# Conn_pcb2.net
KiCad netlist of a schematic drawn in EAGLE
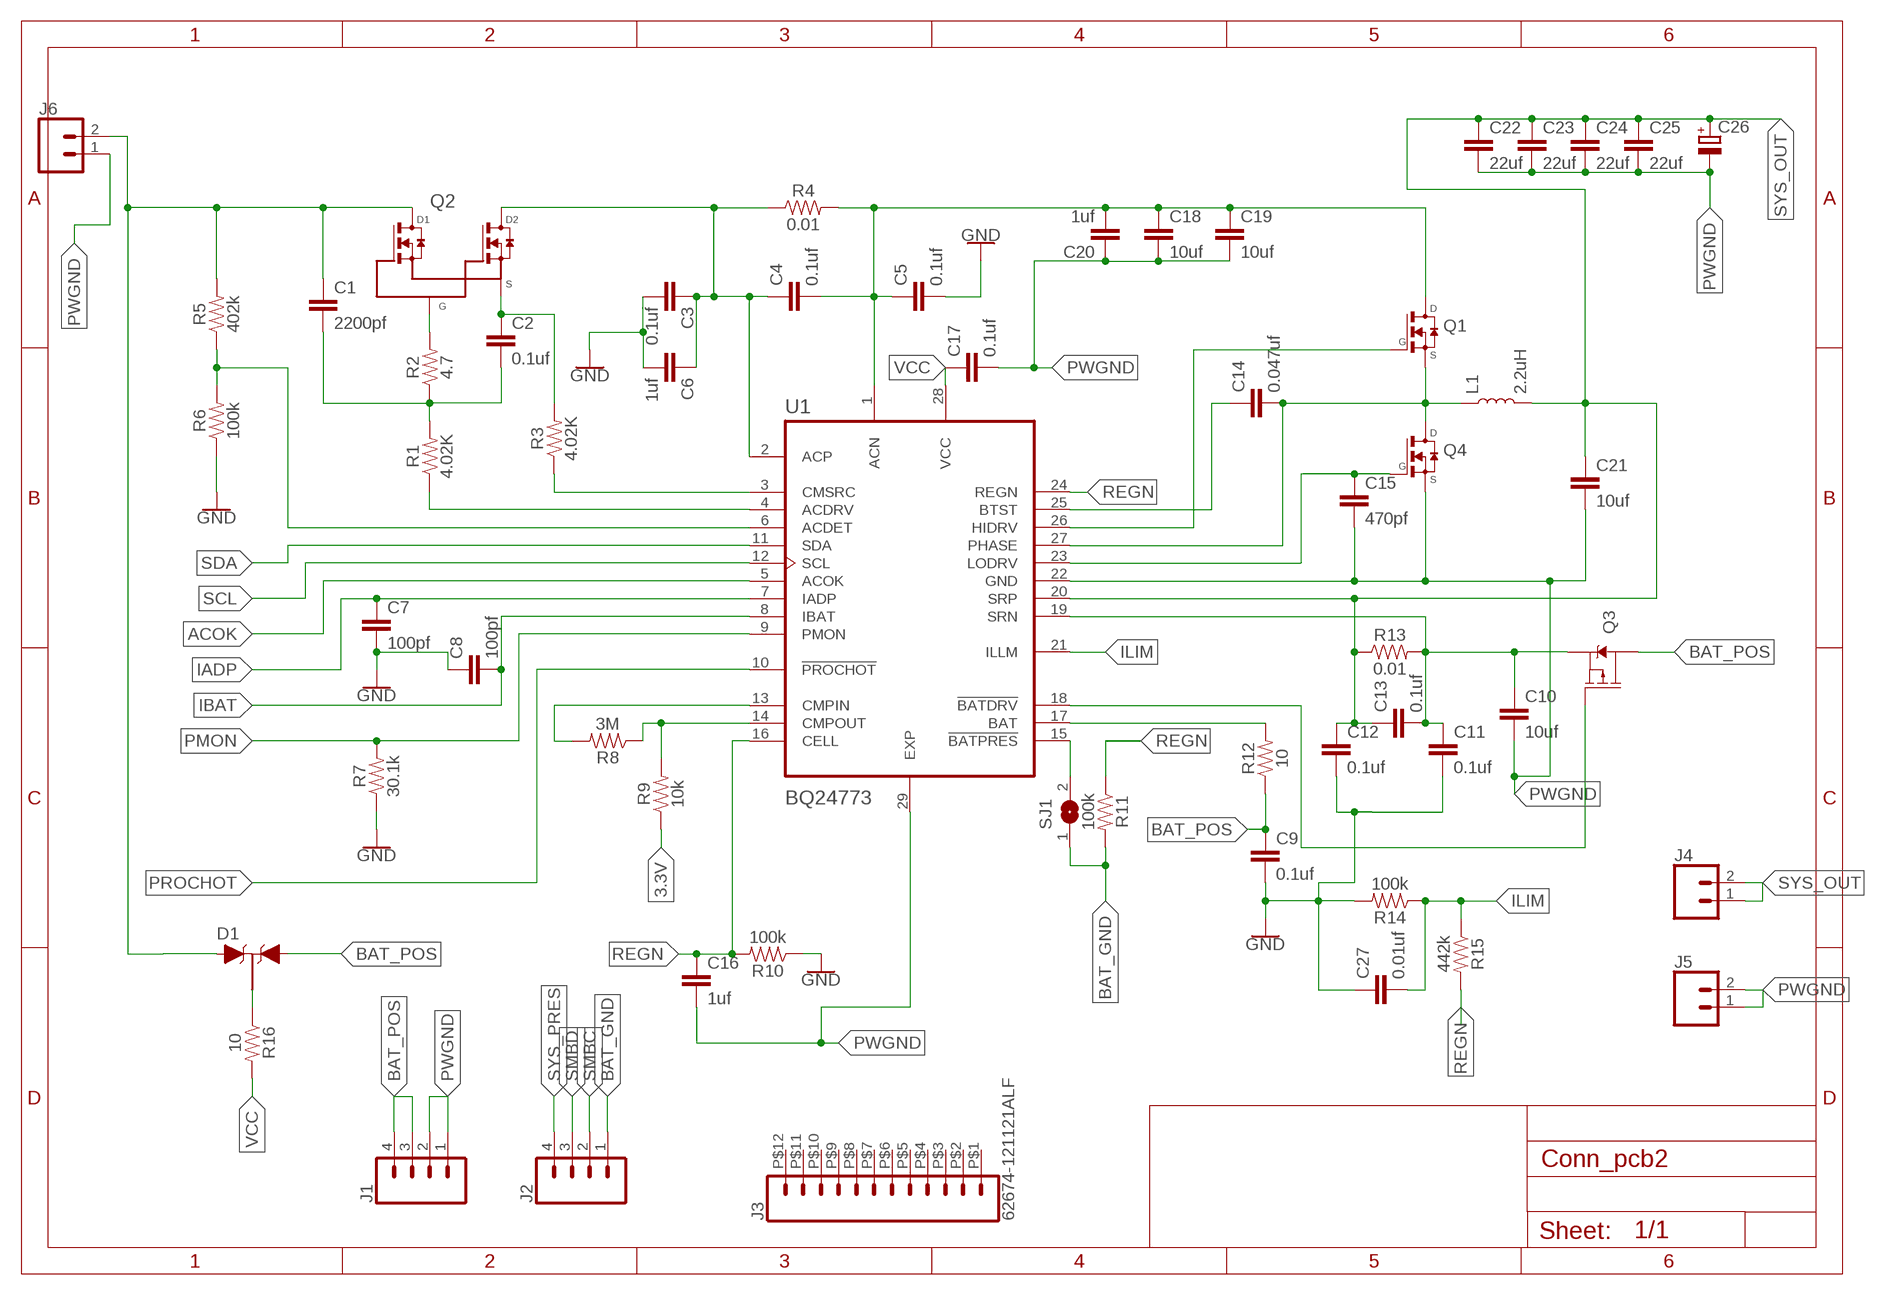
[diagram p0: schematic, sheet 1]

(export (version "E")
  (design (tool "Eeschema 10.0.6"))
  (components
    (comp (ref "C1")
      (value "2200pf")
      (footprint "eagle-import:CAPC1005X50")
      (libsource (lib "eagle-import") (part "CAP0402"))
    )
    (comp (ref "C2")
      (value "0.1uf")
      (footprint "eagle-import:CAPC1005X50")
      (libsource (lib "eagle-import") (part "CAP0402"))
    )
    (comp (ref "C3")
      (value "0.1uf")
      (footprint "eagle-import:CAPC1005X50")
      (libsource (lib "eagle-import") (part "CAP0402"))
    )
    (comp (ref "C4")
      (value "0.1uf")
      (footprint "eagle-import:CAPC1005X50")
      (libsource (lib "eagle-import") (part "CAP0402"))
    )
    (comp (ref "C5")
      (value "0.1uf")
      (footprint "eagle-import:CAPC1005X50")
      (libsource (lib "eagle-import") (part "CAP0402"))
    )
    (comp (ref "C6")
      (value "1uf")
      (footprint "eagle-import:CAPC1005X50")
      (libsource (lib "eagle-import") (part "CAP0402"))
    )
    (comp (ref "C7")
      (value "100pf")
      (footprint "eagle-import:CAPC1005X50")
      (libsource (lib "eagle-import") (part "CAP0402"))
    )
    (comp (ref "C8")
      (value "100pf")
      (footprint "eagle-import:CAPC1005X50")
      (libsource (lib "eagle-import") (part "CAP0402"))
    )
    (comp (ref "C9")
      (value "0.1uf")
      (footprint "eagle-import:CAPC1005X50")
      (libsource (lib "eagle-import") (part "CAP0402"))
    )
    (comp (ref "C10")
      (value "10uf")
      (footprint "eagle-import:C0805K")
      (libsource (lib "eagle-import") (part "C-EUC0805K"))
    )
    (comp (ref "C11")
      (value "0.1uf")
      (footprint "eagle-import:CAPC1005X50")
      (libsource (lib "eagle-import") (part "CAP0402"))
    )
    (comp (ref "C12")
      (value "0.1uf")
      (footprint "eagle-import:CAPC1005X50")
      (libsource (lib "eagle-import") (part "CAP0402"))
    )
    (comp (ref "C13")
      (value "0.1uf")
      (footprint "eagle-import:CAPC1005X50")
      (libsource (lib "eagle-import") (part "CAP0402"))
    )
    (comp (ref "C14")
      (value "0.047uf")
      (footprint "eagle-import:CAPC1005X50")
      (libsource (lib "eagle-import") (part "CAP0402"))
    )
    (comp (ref "C15")
      (value "470pf")
      (footprint "eagle-import:CAPC1005X50")
      (libsource (lib "eagle-import") (part "CAP0402"))
    )
    (comp (ref "C16")
      (value "1uf")
      (footprint "eagle-import:CAPC1005X50")
      (libsource (lib "eagle-import") (part "CAP0402"))
    )
    (comp (ref "C17")
      (value "0.1uf")
      (footprint "eagle-import:CAPC1005X50")
      (libsource (lib "eagle-import") (part "CAP0402"))
    )
    (comp (ref "C18")
      (value "10uf")
      (footprint "eagle-import:C0805K")
      (libsource (lib "eagle-import") (part "C-EUC0805K"))
    )
    (comp (ref "C19")
      (value "10uf")
      (footprint "eagle-import:C0805K")
      (libsource (lib "eagle-import") (part "C-EUC0805K"))
    )
    (comp (ref "C20")
      (value "1uf")
      (footprint "eagle-import:CAPC1005X50")
      (libsource (lib "eagle-import") (part "CAP0402"))
    )
    (comp (ref "C21")
      (value "10uf")
      (footprint "eagle-import:C0805K")
      (libsource (lib "eagle-import") (part "C-EUC0805K"))
    )
    (comp (ref "C22")
      (value "22uf")
      (footprint "eagle-import:C1206")
      (libsource (lib "eagle-import") (part "C-EUC1206"))
    )
    (comp (ref "C23")
      (value "22uf")
      (footprint "eagle-import:C1206")
      (libsource (lib "eagle-import") (part "C-EUC1206"))
    )
    (comp (ref "C24")
      (value "22uf")
      (footprint "eagle-import:C1206")
      (libsource (lib "eagle-import") (part "C-EUC1206"))
    )
    (comp (ref "C25")
      (value "22uf")
      (footprint "eagle-import:C1206")
      (libsource (lib "eagle-import") (part "C-EUC1206"))
    )
    (comp (ref "C26")
      (value "CPOL-EUF")
      (footprint "eagle-import:PANASONIC_F")
      (libsource (lib "eagle-import") (part "CPOL-EUF"))
    )
    (comp (ref "C27")
      (value "0.01uf")
      (footprint "eagle-import:CAPC1005X50")
      (libsource (lib "eagle-import") (part "CAP0402"))
    )
    (comp (ref "D1")
      (value "BAT54C-7-F")
      (footprint "eagle-import:SOT95P235X110-3")
      (libsource (lib "eagle-import") (part "BAT54C-7-F"))
    )
    (comp (ref "J1")
      (value "CONN_041.3")
      (footprint "eagle-import:1X04_NO_SILK_1.3")
      (libsource (lib "eagle-import") (part "CONN_041.3"))
    )
    (comp (ref "J2")
      (value "CONN_041.3")
      (footprint "eagle-import:1X04_NO_SILK_1.3")
      (libsource (lib "eagle-import") (part "CONN_041.3"))
    )
    (comp (ref "J3")
      (value "62674-121121ALF")
      (footprint "eagle-import:62674-121121ALF")
      (libsource (lib "eagle-import") (part "62674-121121ALF"))
    )
    (comp (ref "J4")
      (value "CONN_021.4HOLE")
      (footprint "eagle-import:1X02_1.4HOLE")
      (libsource (lib "eagle-import") (part "CONN_021.4HOLE"))
    )
    (comp (ref "J5")
      (value "CONN_021.4HOLE")
      (footprint "eagle-import:1X02_1.4HOLE")
      (libsource (lib "eagle-import") (part "CONN_021.4HOLE"))
    )
    (comp (ref "J6")
      (value "CONN_021.4HOLE")
      (footprint "eagle-import:1X02_1.4HOLE")
      (libsource (lib "eagle-import") (part "CONN_021.4HOLE"))
    )
    (comp (ref "L1")
      (value "2.2uH")
      (footprint "eagle-import:RESM6365X610")
      (libsource (lib "eagle-import") (part "XEL6060-222MEB"))
    )
    (comp (ref "Q1")
      (value "CSD17308Q3")
      (footprint "eagle-import:SON65P330X330X110-8")
      (fields (field (name "SPICEPREFIX") "Q"))
      (libsource (lib "eagle-import") (part "CSD17308Q3"))
    )
    (comp (ref "Q2")
      (value "CSD87312Q3EVSON")
      (footprint "eagle-import:QFN65P330X330X100-12")
      (libsource (lib "eagle-import") (part "CSD87312Q3EVSON"))
    )
    (comp (ref "Q3")
      (value "CSD25402Q3A")
      (footprint "eagle-import:CSD25402Q3A")
      (libsource (lib "eagle-import") (part "CSD25402Q3A"))
    )
    (comp (ref "Q4")
      (value "CSD17308Q3")
      (footprint "eagle-import:SON65P330X330X110-8")
      (fields (field (name "SPICEPREFIX") "Q"))
      (libsource (lib "eagle-import") (part "CSD17308Q3"))
    )
    (comp (ref "R1")
      (value "4.02K")
      (footprint "eagle-import:0402")
      (libsource (lib "eagle-import") (part "RES4K04020402"))
    )
    (comp (ref "R2")
      (value "4.7")
      (footprint "eagle-import:0402")
      (libsource (lib "eagle-import") (part "RES4K04020402"))
    )
    (comp (ref "R3")
      (value "4.02K")
      (footprint "eagle-import:0402")
      (libsource (lib "eagle-import") (part "RES4K04020402"))
    )
    (comp (ref "R4")
      (value "0.01")
      (footprint "eagle-import:1206")
      (libsource (lib "eagle-import") (part "SENSE-RES"))
    )
    (comp (ref "R5")
      (value "402k")
      (footprint "eagle-import:0402")
      (libsource (lib "eagle-import") (part "RES4K04020402"))
    )
    (comp (ref "R6")
      (value "100k")
      (footprint "eagle-import:0402")
      (libsource (lib "eagle-import") (part "RES4K04020402"))
    )
    (comp (ref "R7")
      (value "30.1k")
      (footprint "eagle-import:0402")
      (libsource (lib "eagle-import") (part "RES4K04020402"))
    )
    (comp (ref "R8")
      (value "3M")
      (footprint "eagle-import:0402")
      (libsource (lib "eagle-import") (part "RES4K04020402"))
    )
    (comp (ref "R9")
      (value "10k")
      (footprint "eagle-import:0402")
      (libsource (lib "eagle-import") (part "RES4K04020402"))
    )
    (comp (ref "R10")
      (value "100k")
      (footprint "eagle-import:0402")
      (libsource (lib "eagle-import") (part "RES4K04020402"))
    )
    (comp (ref "R11")
      (value "100k")
      (footprint "eagle-import:0402")
      (libsource (lib "eagle-import") (part "RES4K04020402"))
    )
    (comp (ref "R12")
      (value "10")
      (footprint "eagle-import:0402")
      (libsource (lib "eagle-import") (part "RES4K04020402"))
    )
    (comp (ref "R13")
      (value "0.01")
      (footprint "eagle-import:1206")
      (libsource (lib "eagle-import") (part "SENSE-RES"))
    )
    (comp (ref "R14")
      (value "100k")
      (footprint "eagle-import:0402")
      (libsource (lib "eagle-import") (part "RES4K04020402"))
    )
    (comp (ref "R15")
      (value "442k")
      (footprint "eagle-import:0402")
      (libsource (lib "eagle-import") (part "RES4K04020402"))
    )
    (comp (ref "R16")
      (value "10")
      (footprint "eagle-import:0402")
      (libsource (lib "eagle-import") (part "RES4K04020402"))
    )
    (comp (ref "SJ1") (value "SJ") (footprint "eagle-import:SJ") (libsource (lib "eagle-import") (part "SJ")))
    (comp (ref "U1")
      (value "BQ24773")
      (footprint "eagle-import:QFN40P400X400X80-29T240")
      (libsource (lib "eagle-import") (part "BQ24773"))
    )
  )
  (nets
    (net (code "1") (name "3.3V") (class "Default")
      (node (ref "R9") (pin "1") (pinfunction "1_1") (pintype "passive"))
    )
    (net (code "2") (name "ACOK") (class "Default")
      (node (ref "U1") (pin "5") (pinfunction "ACOK_5") (pintype "output"))
    )
    (net (code "3") (name "BAT_GND") (class "Default")
      (node (ref "J2") (pin "1") (pinfunction "1_1") (pintype "passive"))
      (node (ref "R11") (pin "2") (pinfunction "2_2") (pintype "passive"))
      (node (ref "SJ1") (pin "1") (pinfunction "1_1") (pintype "passive"))
    )
    (net (code "4") (name "BAT_POS") (class "Default")
      (node (ref "C9") (pin "1") (pinfunction "1_1") (pintype "passive"))
      (node (ref "D1") (pin "2") (pinfunction "A2_2") (pintype "passive"))
      (node (ref "J1") (pin "3") (pinfunction "3_3") (pintype "passive"))
      (node (ref "J1") (pin "4") (pinfunction "4_4") (pintype "passive"))
      (node (ref "Q3") (pin "1") (pinfunction "D_1") (pintype "bidirectional"))
      (node (ref "Q3") (pin "2") (pinfunction "D_2") (pintype "bidirectional"))
      (node (ref "Q3") (pin "3") (pinfunction "D_3") (pintype "bidirectional"))
      (node (ref "R12") (pin "1") (pinfunction "1_1") (pintype "passive"))
    )
    (net (code "5") (name "GND") (class "Default")
      (node (ref "C11") (pin "2") (pinfunction "2_2") (pintype "passive"))
      (node (ref "C12") (pin "2") (pinfunction "2_2") (pintype "passive"))
      (node (ref "C27") (pin "1") (pinfunction "1_1") (pintype "passive"))
      (node (ref "C3") (pin "2") (pinfunction "2_2") (pintype "passive"))
      (node (ref "C5") (pin "2") (pinfunction "2_2") (pintype "passive"))
      (node (ref "C6") (pin "2") (pinfunction "2_2") (pintype "passive"))
      (node (ref "C7") (pin "2") (pinfunction "2_2") (pintype "passive"))
      (node (ref "C8") (pin "1") (pinfunction "1_1") (pintype "passive"))
      (node (ref "C9") (pin "2") (pinfunction "2_2") (pintype "passive"))
      (node (ref "R10") (pin "1") (pinfunction "1_1") (pintype "passive"))
      (node (ref "R14") (pin "2") (pinfunction "2_2") (pintype "passive"))
      (node (ref "R6") (pin "1") (pinfunction "1_1") (pintype "passive"))
      (node (ref "R7") (pin "1") (pinfunction "1_1") (pintype "passive"))
    )
    (net (code "6") (name "IADP") (class "Default")
      (node (ref "C7") (pin "1") (pinfunction "1_1") (pintype "passive"))
      (node (ref "U1") (pin "7") (pinfunction "IADP_7") (pintype "output"))
    )
    (net (code "7") (name "IBAT") (class "Default")
      (node (ref "C8") (pin "2") (pinfunction "2_2") (pintype "passive"))
      (node (ref "U1") (pin "8") (pinfunction "IBAT_8") (pintype "output"))
    )
    (net (code "8") (name "ILIM") (class "Default")
      (node (ref "C27") (pin "2") (pinfunction "2_2") (pintype "passive"))
      (node (ref "R14") (pin "1") (pinfunction "1_1") (pintype "passive"))
      (node (ref "R15") (pin "1") (pinfunction "1_1") (pintype "passive"))
      (node (ref "U1") (pin "21") (pinfunction "ILLM_21") (pintype "input"))
    )
    (net (code "9") (name "Net-(C1-Pad2)") (class "Default")
      (node (ref "C1") (pin "2") (pinfunction "2_2") (pintype "passive"))
      (node (ref "C2") (pin "2") (pinfunction "2_2") (pintype "passive"))
      (node (ref "R1") (pin "2") (pinfunction "2_2") (pintype "passive"))
      (node (ref "R2") (pin "1") (pinfunction "1_1") (pintype "passive"))
    )
    (net (code "10") (name "Net-(C2-Pad1)") (class "Default")
      (node (ref "C2") (pin "1") (pinfunction "1_1") (pintype "passive"))
      (node (ref "Q2") (pin "9") (pinfunction "S_9") (pintype "passive"))
      (node (ref "Q2") (pin "9.1") (pinfunction "S_9.1") (pintype "passive"))
      (node (ref "Q2") (pin "9.2") (pinfunction "S_9.2") (pintype "passive"))
      (node (ref "Q2") (pin "9.3") (pinfunction "S_9.3") (pintype "passive"))
      (node (ref "Q2") (pin "9.4") (pinfunction "S_9.4") (pintype "passive"))
      (node (ref "R3") (pin "2") (pinfunction "2_2") (pintype "passive"))
    )
    (net (code "11") (name "Net-(D1-A1)") (class "Default")
      (node (ref "C1") (pin "1") (pinfunction "1_1") (pintype "passive"))
      (node (ref "D1") (pin "1") (pinfunction "A1_1") (pintype "passive"))
      (node (ref "J6") (pin "2") (pinfunction "2_2") (pintype "passive"))
      (node (ref "Q2") (pin "1") (pinfunction "D1_1") (pintype "passive"))
      (node (ref "Q2") (pin "3") (pinfunction "D1_3") (pintype "passive"))
      (node (ref "Q2") (pin "4") (pinfunction "D1_4") (pintype "passive"))
      (node (ref "R5") (pin "2") (pinfunction "2_2") (pintype "passive"))
    )
    (net (code "12") (name "Net-(D1-K)") (class "Default")
      (node (ref "D1") (pin "3") (pinfunction "K_3") (pintype "passive"))
      (node (ref "R16") (pin "1") (pinfunction "1_1") (pintype "passive"))
    )
    (net (code "13") (name "Net-(Q1-G)") (class "Default")
      (node (ref "Q1") (pin "4") (pinfunction "G_4") (pintype "passive"))
      (node (ref "U1") (pin "26") (pinfunction "HIDRV_26") (pintype "output"))
    )
    (net (code "14") (name "Net-(Q2-G)") (class "Default")
      (node (ref "Q2") (pin "5") (pinfunction "G_5") (pintype "passive"))
      (node (ref "R2") (pin "2") (pinfunction "2_2") (pintype "passive"))
    )
    (net (code "15") (name "Net-(Q3-G)") (class "Default")
      (node (ref "Q3") (pin "4") (pinfunction "G_4") (pintype "bidirectional"))
      (node (ref "U1") (pin "18") (pinfunction "~{BATDRV}_18") (pintype "output"))
    )
    (net (code "16") (name "Net-(Q4-G)") (class "Default")
      (node (ref "C15") (pin "1") (pinfunction "1_1") (pintype "passive"))
      (node (ref "Q4") (pin "4") (pinfunction "G_4") (pintype "passive"))
      (node (ref "U1") (pin "23") (pinfunction "LODRV_23") (pintype "output"))
    )
    (net (code "17") (name "Net-(U1-ACDET)") (class "Default")
      (node (ref "R5") (pin "1") (pinfunction "1_1") (pintype "passive"))
      (node (ref "R6") (pin "2") (pinfunction "2_2") (pintype "passive"))
      (node (ref "U1") (pin "6") (pinfunction "ACDET_6") (pintype "input"))
    )
    (net (code "18") (name "Net-(U1-ACDRV)") (class "Default")
      (node (ref "R1") (pin "1") (pinfunction "1_1") (pintype "passive"))
      (node (ref "U1") (pin "4") (pinfunction "ACDRV_4") (pintype "output"))
    )
    (net (code "19") (name "Net-(U1-ACN)") (class "Default")
      (node (ref "C18") (pin "1") (pinfunction "1_1") (pintype "passive"))
      (node (ref "C19") (pin "1") (pinfunction "1_1") (pintype "passive"))
      (node (ref "C20") (pin "2") (pinfunction "2_2") (pintype "passive"))
      (node (ref "C4") (pin "2") (pinfunction "2_2") (pintype "passive"))
      (node (ref "C5") (pin "1") (pinfunction "1_1") (pintype "passive"))
      (node (ref "Q1") (pin "5") (pinfunction "D_5") (pintype "passive"))
      (node (ref "Q1") (pin "6") (pinfunction "D_6") (pintype "passive"))
      (node (ref "Q1") (pin "7") (pinfunction "D_7") (pintype "passive"))
      (node (ref "Q1") (pin "8") (pinfunction "D_8") (pintype "passive"))
      (node (ref "R4") (pin "2") (pinfunction "2_2") (pintype "passive"))
      (node (ref "U1") (pin "1") (pinfunction "ACN_1") (pintype "input"))
    )
    (net (code "20") (name "Net-(U1-ACP)") (class "Default")
      (node (ref "C3") (pin "1") (pinfunction "1_1") (pintype "passive"))
      (node (ref "C4") (pin "1") (pinfunction "1_1") (pintype "passive"))
      (node (ref "C6") (pin "1") (pinfunction "1_1") (pintype "passive"))
      (node (ref "Q2") (pin "6") (pinfunction "D2_6") (pintype "passive"))
      (node (ref "Q2") (pin "7") (pinfunction "D2_7") (pintype "passive"))
      (node (ref "Q2") (pin "8") (pinfunction "D2_8") (pintype "passive"))
      (node (ref "R4") (pin "1") (pinfunction "1_1") (pintype "passive"))
      (node (ref "U1") (pin "2") (pinfunction "ACP_2") (pintype "input"))
    )
    (net (code "21") (name "Net-(U1-BAT)") (class "Default")
      (node (ref "R12") (pin "2") (pinfunction "2_2") (pintype "passive"))
      (node (ref "U1") (pin "17") (pinfunction "BAT_17") (pintype "input"))
    )
    (net (code "22") (name "Net-(U1-BTST)") (class "Default")
      (node (ref "C14") (pin "1") (pinfunction "1_1") (pintype "passive"))
      (node (ref "U1") (pin "25") (pinfunction "BTST_25") (pintype "passive"))
    )
    (net (code "23") (name "Net-(U1-CMPIN)") (class "Default")
      (node (ref "R8") (pin "2") (pinfunction "2_2") (pintype "passive"))
      (node (ref "U1") (pin "13") (pinfunction "CMPIN_13") (pintype "input"))
    )
    (net (code "24") (name "Net-(U1-CMPOUT)") (class "Default")
      (node (ref "R8") (pin "1") (pinfunction "1_1") (pintype "passive"))
      (node (ref "R9") (pin "2") (pinfunction "2_2") (pintype "passive"))
      (node (ref "U1") (pin "14") (pinfunction "CMPOUT_14") (pintype "output"))
    )
    (net (code "25") (name "Net-(U1-CMSRC)") (class "Default")
      (node (ref "R3") (pin "1") (pinfunction "1_1") (pintype "passive"))
      (node (ref "U1") (pin "3") (pinfunction "CMSRC_3") (pintype "input"))
    )
    (net (code "26") (name "Net-(U1-PHASE)") (class "Default")
      (node (ref "C14") (pin "2") (pinfunction "2_2") (pintype "passive"))
      (node (ref "L1") (pin "1") (pinfunction "1_1") (pintype "passive"))
      (node (ref "Q1") (pin "1") (pinfunction "S_1") (pintype "passive"))
      (node (ref "Q1") (pin "2") (pinfunction "S_2") (pintype "passive"))
      (node (ref "Q1") (pin "3") (pinfunction "S_3") (pintype "passive"))
      (node (ref "Q4") (pin "5") (pinfunction "D_5") (pintype "passive"))
      (node (ref "Q4") (pin "6") (pinfunction "D_6") (pintype "passive"))
      (node (ref "Q4") (pin "7") (pinfunction "D_7") (pintype "passive"))
      (node (ref "Q4") (pin "8") (pinfunction "D_8") (pintype "passive"))
      (node (ref "U1") (pin "27") (pinfunction "PHASE_27") (pintype "output"))
    )
    (net (code "27") (name "Net-(U1-SRN)") (class "Default")
      (node (ref "C10") (pin "1") (pinfunction "1_1") (pintype "passive"))
      (node (ref "C11") (pin "1") (pinfunction "1_1") (pintype "passive"))
      (node (ref "C13") (pin "2") (pinfunction "2_2") (pintype "passive"))
      (node (ref "Q3") (pin "5") (pinfunction "S_5") (pintype "bidirectional"))
      (node (ref "Q3") (pin "6") (pinfunction "S_6") (pintype "bidirectional"))
      (node (ref "Q3") (pin "7") (pinfunction "S_7") (pintype "bidirectional"))
      (node (ref "Q3") (pin "8") (pinfunction "S_8") (pintype "bidirectional"))
      (node (ref "Q3") (pin "9") (pinfunction "S_9") (pintype "bidirectional"))
      (node (ref "R13") (pin "2") (pinfunction "2_2") (pintype "passive"))
      (node (ref "U1") (pin "19") (pinfunction "SRN_19") (pintype "input"))
    )
    (net (code "28") (name "Net-(U1-~{BATPRES})") (class "Default")
      (node (ref "SJ1") (pin "2") (pinfunction "2_2") (pintype "passive"))
      (node (ref "U1") (pin "15") (pinfunction "~{BATPRES}_15") (pintype "input"))
    )
    (net (code "29") (name "PMON") (class "Default")
      (node (ref "R7") (pin "2") (pinfunction "2_2") (pintype "passive"))
      (node (ref "U1") (pin "9") (pinfunction "PMON_9") (pintype "output"))
    )
    (net (code "30") (name "PROCHOT") (class "Default")
      (node (ref "U1") (pin "10") (pinfunction "~{PROCHOT}_10") (pintype "output"))
    )
    (net (code "31") (name "PWGND") (class "Default")
      (node (ref "C10") (pin "2") (pinfunction "2_2") (pintype "passive"))
      (node (ref "C15") (pin "2") (pinfunction "2_2") (pintype "passive"))
      (node (ref "C16") (pin "2") (pinfunction "2_2") (pintype "passive"))
      (node (ref "C17") (pin "2") (pinfunction "2_2") (pintype "passive"))
      (node (ref "C18") (pin "2") (pinfunction "2_2") (pintype "passive"))
      (node (ref "C19") (pin "2") (pinfunction "2_2") (pintype "passive"))
      (node (ref "C20") (pin "1") (pinfunction "1_1") (pintype "passive"))
      (node (ref "C21") (pin "2") (pinfunction "2_2") (pintype "passive"))
      (node (ref "C22") (pin "2") (pinfunction "2_2") (pintype "passive"))
      (node (ref "C23") (pin "2") (pinfunction "2_2") (pintype "passive"))
      (node (ref "C24") (pin "2") (pinfunction "2_2") (pintype "passive"))
      (node (ref "C25") (pin "2") (pinfunction "2_2") (pintype "passive"))
      (node (ref "C26") (pin "-") (pinfunction "-_-") (pintype "passive"))
      (node (ref "J1") (pin "1") (pinfunction "1_1") (pintype "passive"))
      (node (ref "J1") (pin "2") (pinfunction "2_2") (pintype "passive"))
      (node (ref "J5") (pin "1") (pinfunction "1_1") (pintype "passive"))
      (node (ref "J5") (pin "2") (pinfunction "2_2") (pintype "passive"))
      (node (ref "J6") (pin "1") (pinfunction "1_1") (pintype "passive"))
      (node (ref "Q4") (pin "1") (pinfunction "S_1") (pintype "passive"))
      (node (ref "Q4") (pin "2") (pinfunction "S_2") (pintype "passive"))
      (node (ref "Q4") (pin "3") (pinfunction "S_3") (pintype "passive"))
      (node (ref "U1") (pin "22") (pinfunction "GND_22") (pintype "power_in"))
      (node (ref "U1") (pin "29") (pinfunction "EXP_29") (pintype "power_in"))
    )
    (net (code "32") (name "REGN") (class "Default")
      (node (ref "C16") (pin "1") (pinfunction "1_1") (pintype "passive"))
      (node (ref "R10") (pin "2") (pinfunction "2_2") (pintype "passive"))
      (node (ref "R11") (pin "1") (pinfunction "1_1") (pintype "passive"))
      (node (ref "R15") (pin "2") (pinfunction "2_2") (pintype "passive"))
      (node (ref "U1") (pin "16") (pinfunction "CELL_16") (pintype "input"))
      (node (ref "U1") (pin "24") (pinfunction "REGN_24") (pintype "output"))
    )
    (net (code "33") (name "SCL") (class "Default")
      (node (ref "U1") (pin "12") (pinfunction "SCL_12") (pintype "input"))
    )
    (net (code "34") (name "SDA") (class "Default")
      (node (ref "U1") (pin "11") (pinfunction "SDA_11") (pintype "bidirectional"))
    )
    (net (code "35") (name "SMBC") (class "Default")
      (node (ref "J2") (pin "2") (pinfunction "2_2") (pintype "passive"))
    )
    (net (code "36") (name "SMBD") (class "Default")
      (node (ref "J2") (pin "3") (pinfunction "3_3") (pintype "passive"))
    )
    (net (code "37") (name "SYS_OUT") (class "Default")
      (node (ref "C12") (pin "1") (pinfunction "1_1") (pintype "passive"))
      (node (ref "C13") (pin "1") (pinfunction "1_1") (pintype "passive"))
      (node (ref "C21") (pin "1") (pinfunction "1_1") (pintype "passive"))
      (node (ref "C22") (pin "1") (pinfunction "1_1") (pintype "passive"))
      (node (ref "C23") (pin "1") (pinfunction "1_1") (pintype "passive"))
      (node (ref "C24") (pin "1") (pinfunction "1_1") (pintype "passive"))
      (node (ref "C25") (pin "1") (pinfunction "1_1") (pintype "passive"))
      (node (ref "C26") (pin "+") (pinfunction "+_+") (pintype "passive"))
      (node (ref "J4") (pin "1") (pinfunction "1_1") (pintype "passive"))
      (node (ref "J4") (pin "2") (pinfunction "2_2") (pintype "passive"))
      (node (ref "L1") (pin "2") (pinfunction "2_2") (pintype "passive"))
      (node (ref "R13") (pin "1") (pinfunction "1_1") (pintype "passive"))
      (node (ref "U1") (pin "20") (pinfunction "SRP_20") (pintype "input"))
    )
    (net (code "38") (name "SYS_PRES") (class "Default")
      (node (ref "J2") (pin "4") (pinfunction "4_4") (pintype "passive"))
    )
    (net (code "39") (name "VCC") (class "Default")
      (node (ref "C17") (pin "1") (pinfunction "1_1") (pintype "passive"))
      (node (ref "R16") (pin "2") (pinfunction "2_2") (pintype "passive"))
      (node (ref "U1") (pin "28") (pinfunction "VCC_28") (pintype "power_in"))
    )
    (net (code "40") (name "unconnected-(J3-1-PadP$1)") (class "Default")
      (node (ref "J3") (pin "P$1") (pinfunction "1_P$1") (pintype "passive"))
    )
    (net (code "41") (name "unconnected-(J3-2-PadP$2)") (class "Default")
      (node (ref "J3") (pin "P$2") (pinfunction "2_P$2") (pintype "passive"))
    )
    (net (code "42") (name "unconnected-(J3-3-PadP$3)") (class "Default")
      (node (ref "J3") (pin "P$3") (pinfunction "3_P$3") (pintype "passive"))
    )
    (net (code "43") (name "unconnected-(J3-4-PadP$4)") (class "Default")
      (node (ref "J3") (pin "P$4") (pinfunction "4_P$4") (pintype "passive"))
    )
    (net (code "44") (name "unconnected-(J3-5-PadP$5)") (class "Default")
      (node (ref "J3") (pin "P$5") (pinfunction "5_P$5") (pintype "passive"))
    )
    (net (code "45") (name "unconnected-(J3-6-PadP$6)") (class "Default")
      (node (ref "J3") (pin "P$6") (pinfunction "6_P$6") (pintype "passive"))
    )
    (net (code "46") (name "unconnected-(J3-7-PadP$7)") (class "Default")
      (node (ref "J3") (pin "P$7") (pinfunction "7_P$7") (pintype "passive"))
    )
    (net (code "47") (name "unconnected-(J3-8-PadP$8)") (class "Default")
      (node (ref "J3") (pin "P$8") (pinfunction "8_P$8") (pintype "passive"))
    )
    (net (code "48") (name "unconnected-(J3-9-PadP$9)") (class "Default")
      (node (ref "J3") (pin "P$9") (pinfunction "9_P$9") (pintype "passive"))
    )
    (net (code "49") (name "unconnected-(J3-10-PadP$10)") (class "Default")
      (node (ref "J3") (pin "P$10") (pinfunction "10_P$10") (pintype "passive"))
    )
    (net (code "50") (name "unconnected-(J3-11-PadP$11)") (class "Default")
      (node (ref "J3") (pin "P$11") (pinfunction "11_P$11") (pintype "passive"))
    )
    (net (code "51") (name "unconnected-(J3-12-PadP$12)") (class "Default")
      (node (ref "J3") (pin "P$12") (pinfunction "12_P$12") (pintype "passive"))
    )
  )
)
